# Keg_Cop_-_Daisy_Chain_RJ45_T_with_Slots.net
KiCad netlist of a schematic drawn in EAGLE
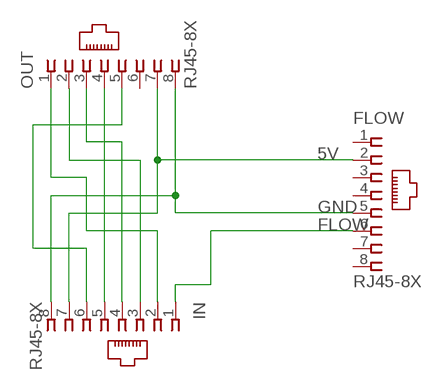
[diagram p0: schematic, sheet 1]

(export (version "E")
  (design (tool "Eeschema 10.0.6"))
  (components
    (comp (ref "FLOW")
      (value "RJ45-8X")
      (footprint "eagle-import:RJ45-NO-SHIELD")
      (libsource (lib "eagle-import") (part "RJ45-8X"))
    )
    (comp (ref "IN")
      (value "RJ45-8X")
      (footprint "eagle-import:RJ45-NO-SHIELD")
      (libsource (lib "eagle-import") (part "RJ45-8X"))
    )
    (comp (ref "OUT")
      (value "RJ45-8X")
      (footprint "eagle-import:RJ45-NO-SHIELD")
      (libsource (lib "eagle-import") (part "RJ45-8X"))
    )
  )
  (nets
    (net (code "1") (name "/5V") (class "Default")
      (node (ref "FLOW") (pin "2") (pinfunction "2_2") (pintype "passive"))
      (node (ref "IN") (pin "7") (pinfunction "7_7") (pintype "passive"))
      (node (ref "OUT") (pin "7") (pinfunction "7_7") (pintype "passive"))
    )
    (net (code "2") (name "/FLOW") (class "Default")
      (node (ref "FLOW") (pin "6") (pinfunction "6_6") (pintype "passive"))
      (node (ref "IN") (pin "1") (pinfunction "1_1") (pintype "passive"))
    )
    (net (code "3") (name "/GND") (class "Default")
      (node (ref "FLOW") (pin "5") (pinfunction "5_5") (pintype "passive"))
      (node (ref "IN") (pin "8") (pinfunction "8_8") (pintype "passive"))
      (node (ref "OUT") (pin "8") (pinfunction "8_8") (pintype "passive"))
    )
    (net (code "4") (name "Net-(IN-Pad2)") (class "Default")
      (node (ref "IN") (pin "2") (pinfunction "2_2") (pintype "passive"))
      (node (ref "OUT") (pin "1") (pinfunction "1_1") (pintype "passive"))
    )
    (net (code "5") (name "Net-(IN-Pad3)") (class "Default")
      (node (ref "IN") (pin "3") (pinfunction "3_3") (pintype "passive"))
      (node (ref "OUT") (pin "2") (pinfunction "2_2") (pintype "passive"))
    )
    (net (code "6") (name "Net-(IN-Pad4)") (class "Default")
      (node (ref "IN") (pin "4") (pinfunction "4_4") (pintype "passive"))
      (node (ref "OUT") (pin "3") (pinfunction "3_3") (pintype "passive"))
    )
    (net (code "7") (name "Net-(IN-Pad5)") (class "Default")
      (node (ref "IN") (pin "5") (pinfunction "5_5") (pintype "passive"))
      (node (ref "OUT") (pin "4") (pinfunction "4_4") (pintype "passive"))
    )
    (net (code "8") (name "Net-(IN-Pad6)") (class "Default")
      (node (ref "IN") (pin "6") (pinfunction "6_6") (pintype "passive"))
      (node (ref "OUT") (pin "5") (pinfunction "5_5") (pintype "passive"))
    )
    (net (code "9") (name "unconnected-(FLOW-Pad1)") (class "Default")
      (node (ref "FLOW") (pin "1") (pinfunction "1_1") (pintype "passive"))
    )
    (net (code "10") (name "unconnected-(FLOW-Pad3)") (class "Default")
      (node (ref "FLOW") (pin "3") (pinfunction "3_3") (pintype "passive"))
    )
    (net (code "11") (name "unconnected-(FLOW-Pad4)") (class "Default")
      (node (ref "FLOW") (pin "4") (pinfunction "4_4") (pintype "passive"))
    )
    (net (code "12") (name "unconnected-(FLOW-Pad7)") (class "Default")
      (node (ref "FLOW") (pin "7") (pinfunction "7_7") (pintype "passive"))
    )
    (net (code "13") (name "unconnected-(FLOW-Pad8)") (class "Default")
      (node (ref "FLOW") (pin "8") (pinfunction "8_8") (pintype "passive"))
    )
    (net (code "14") (name "unconnected-(OUT-Pad6)") (class "Default")
      (node (ref "OUT") (pin "6") (pinfunction "6_6") (pintype "passive"))
    )
  )
)
